# Sheet1.net
KiCad netlist of a schematic drawn in Altium Designer
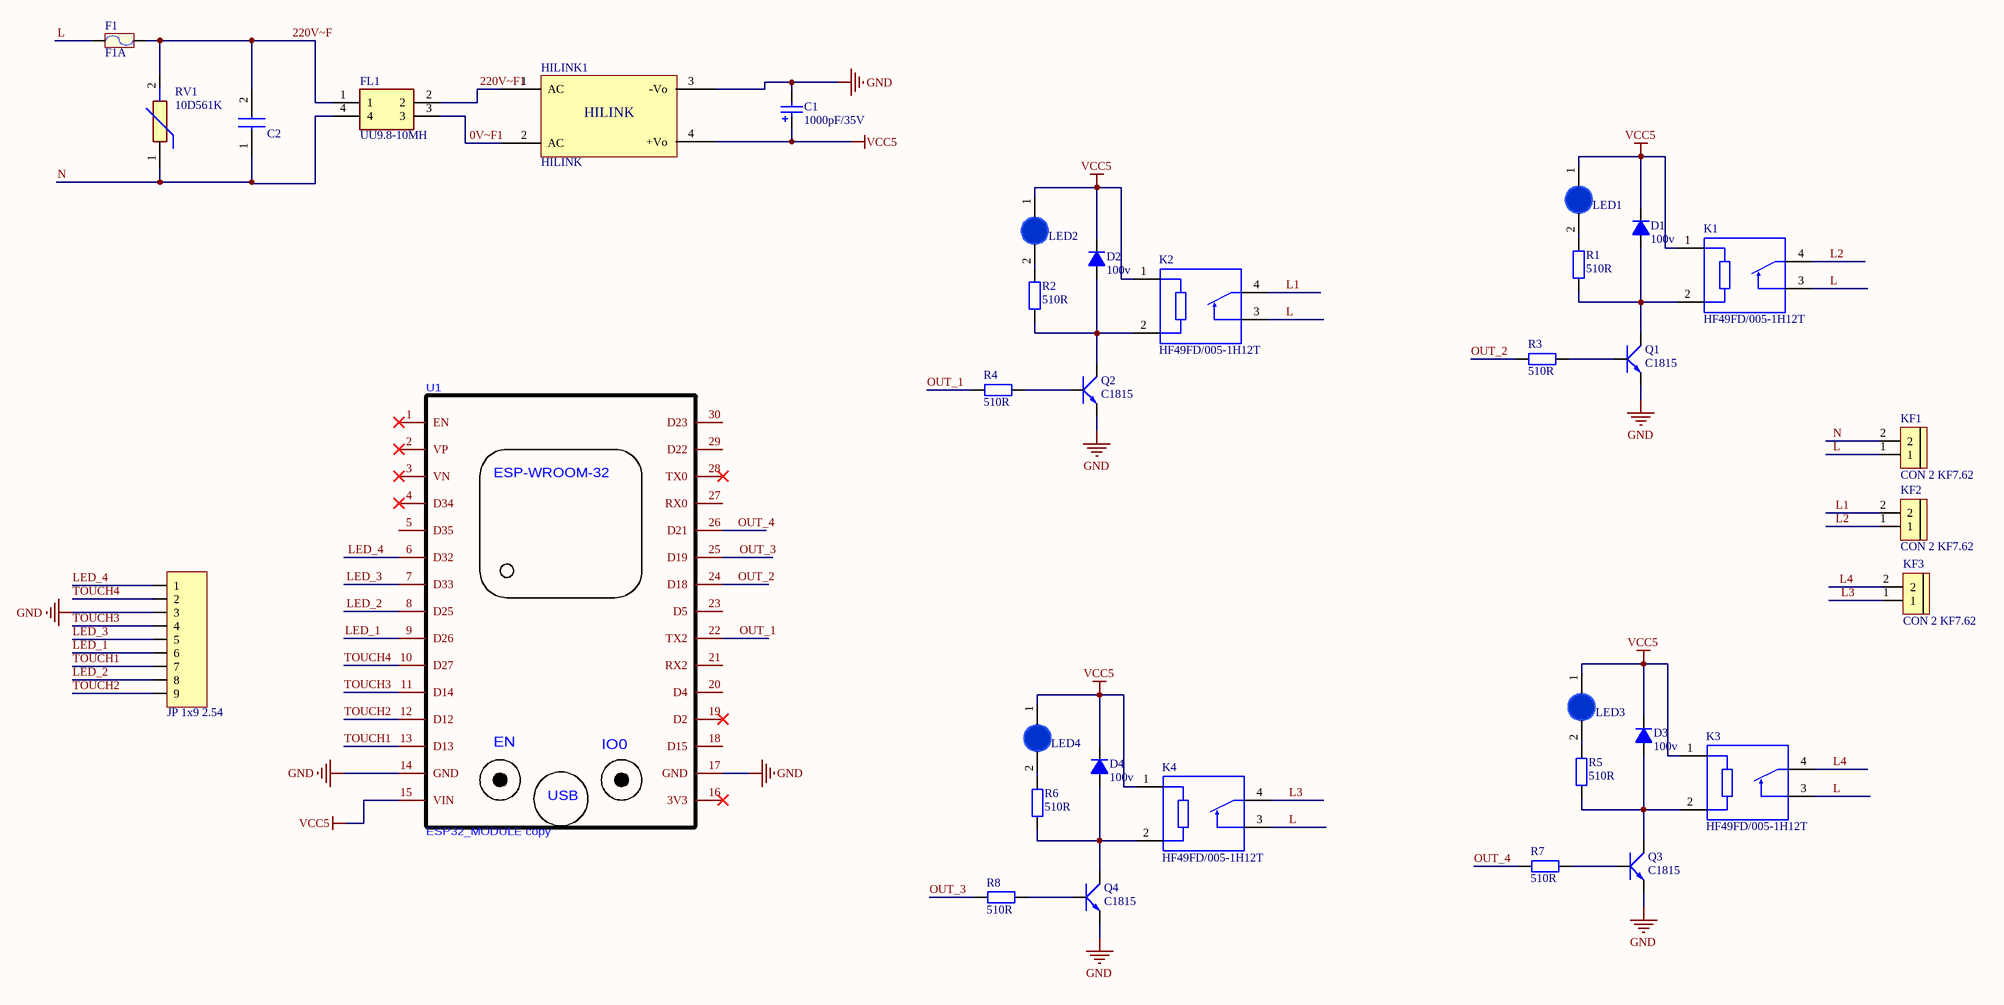
[diagram p0: Sheet1.SchDoc]

(export (version "E")
  (design (tool "Eeschema 10.0.6"))
  (components
    (comp (ref "C1")
      (value "1000pF/35V")
      (footprint "CP2/5")
      (description "Polarized Capacitor (Surface Mount)")
      (fields (field (name "Comment") "Cap Pol3") (field (name "PUBLISHER") "Altium Limited"))
      (libsource (lib "myLib_v1") (part "Cap Pol3"))
    )
    (comp (ref "C2")
      (value "R46KF3100JMP0K")
      (footprint "R46KF3100JMP0K")
      (description "Capacitor")
      (fields (field (name "MOUSER PART NUMBER") "80-R46KF3100JMP0K"))
      (libsource (lib "myLib_v1") (part "R46KF3100JMP0K"))
    )
    (comp (ref "D1")
      (value "100v")
      (footprint "DIODE 0.5A")
      (description "Cắm")
      (libsource (lib "Altium_Lib_by_KhueNguyenCreator") (part "Diode 1N4148"))
    )
    (comp (ref "D2")
      (value "100v")
      (footprint "DIODE 0.5A")
      (description "Cắm")
      (libsource (lib "Altium_Lib_by_KhueNguyenCreator") (part "Diode 1N4148"))
    )
    (comp (ref "D3")
      (value "100v")
      (footprint "DIODE 0.5A")
      (description "Cắm")
      (libsource (lib "Altium_Lib_by_KhueNguyenCreator") (part "Diode 1N4148"))
    )
    (comp (ref "D4")
      (value "100v")
      (footprint "DIODE 0.5A")
      (description "Cắm")
      (libsource (lib "Altium_Lib_by_KhueNguyenCreator") (part "Diode 1N4148"))
    )
    (comp (ref "F1")
      (value "F1A")
      (footprint "Fuse")
      (description "Fuse")
      (fields (field (name "DESIGNED BY") "VanDungEvn"))
      (libsource (lib "myLib_v1") (part "Fuse"))
    )
    (comp (ref "FL1")
      (value "UU9.8-10MH")
      (footprint "UU9810MH")
      (description "Filter")
      (libsource (lib "myLib_v1") (part "UU9.8-10MH"))
    )
    (comp (ref "HILINK1")
      (value "HILINK")
      (footprint "HILINK_1W")
      (libsource (lib "myLib_v1") (part "HILINK"))
    )
    (comp (ref "JP1")
      (value "JP 1x9 2.54")
      (footprint "JP 1x9 CT")
      (description "Cắm")
      (libsource (lib "Altium_Lib_by_KhueNguyenCreator") (part "JP 1x9 2.54 Cai Thang"))
    )
    (comp (ref "K1")
      (value "HF49FD/005-1H12T")
      (footprint "RELAY_HF49FD/005-1H12T")
      (description "Relay: electromagnetic; SPST-NO; Ucoil: 5VDC; 5A/250VAC; 5A/30VDC")
      (fields (field (name "MF") "Hongfa"))
      (libsource (lib "myLib_v1") (part "HF49FD/005-1H12T"))
    )
    (comp (ref "K2")
      (value "HF49FD/005-1H12T")
      (footprint "RELAY_HF49FD/005-1H12T")
      (description "Relay: electromagnetic; SPST-NO; Ucoil: 5VDC; 5A/250VAC; 5A/30VDC")
      (fields (field (name "MF") "Hongfa"))
      (libsource (lib "myLib_v1") (part "HF49FD/005-1H12T"))
    )
    (comp (ref "K3")
      (value "HF49FD/005-1H12T")
      (footprint "RELAY_HF49FD/005-1H12T")
      (description "Relay: electromagnetic; SPST-NO; Ucoil: 5VDC; 5A/250VAC; 5A/30VDC")
      (fields (field (name "MF") "Hongfa"))
      (libsource (lib "myLib_v1") (part "HF49FD/005-1H12T"))
    )
    (comp (ref "K4")
      (value "HF49FD/005-1H12T")
      (footprint "RELAY_HF49FD/005-1H12T")
      (description "Relay: electromagnetic; SPST-NO; Ucoil: 5VDC; 5A/250VAC; 5A/30VDC")
      (fields (field (name "MF") "Hongfa"))
      (libsource (lib "myLib_v1") (part "HF49FD/005-1H12T"))
    )
    (comp (ref "KF1")
      (value "CON 2 KF7.62")
      (footprint "CON 2 KF7.62")
      (description "Cắm")
      (libsource (lib "Altium_Lib_by_KhueNguyenCreator") (part "CON 2 KF7.62"))
    )
    (comp (ref "KF2")
      (value "CON 2 KF7.62")
      (footprint "CON 2 KF7.62")
      (description "Cắm")
      (libsource (lib "Altium_Lib_by_KhueNguyenCreator") (part "CON 2 KF7.62"))
    )
    (comp (ref "KF3")
      (value "CON 2 KF7.62")
      (footprint "CON 2 KF7.62")
      (description "Cắm")
      (libsource (lib "Altium_Lib_by_KhueNguyenCreator") (part "CON 2 KF7.62"))
    )
    (comp (ref "LED1")
      (value "LED 3mm")
      (footprint "LED-3MM-BLUE")
      (description "Cắm")
      (libsource (lib "myLib_v1") (part "LED 3mm Xanh Duong"))
    )
    (comp (ref "LED2")
      (value "LED 3mm")
      (footprint "LED-3MM-BLUE")
      (description "Cắm")
      (libsource (lib "myLib_v1") (part "LED 3mm Xanh Duong"))
    )
    (comp (ref "LED3")
      (value "LED 3mm")
      (footprint "LED-3MM-BLUE")
      (description "Cắm")
      (libsource (lib "myLib_v1") (part "LED 3mm Xanh Duong"))
    )
    (comp (ref "LED4")
      (value "LED 3mm")
      (footprint "LED-3MM-BLUE")
      (description "Cắm")
      (libsource (lib "myLib_v1") (part "LED 3mm Xanh Duong"))
    )
    (comp (ref "Q1")
      (value "C1815")
      (footprint "C1815_cam")
      (description "NPN 600mW, ECB")
      (libsource (lib "myLib_v1") (part "C1815"))
    )
    (comp (ref "Q2")
      (value "C1815")
      (footprint "C1815_cam")
      (description "NPN 600mW, ECB")
      (libsource (lib "myLib_v1") (part "C1815"))
    )
    (comp (ref "Q3")
      (value "C1815")
      (footprint "C1815_cam")
      (description "NPN 600mW, ECB")
      (libsource (lib "myLib_v1") (part "C1815"))
    )
    (comp (ref "Q4")
      (value "C1815")
      (footprint "C1815_cam")
      (description "NPN 600mW, ECB")
      (libsource (lib "myLib_v1") (part "C1815"))
    )
    (comp (ref "R1")
      (value "510R")
      (footprint "R1/4W")
      (description "Resistor 1/4W")
      (libsource (lib "myLib_v1") (part "R1/4W"))
    )
    (comp (ref "R2")
      (value "510R")
      (footprint "R1/4W")
      (description "Resistor 1/4W")
      (libsource (lib "myLib_v1") (part "R1/4W"))
    )
    (comp (ref "R3")
      (value "510R")
      (footprint "R1/4W")
      (description "Resistor 1/4W")
      (libsource (lib "myLib_v1") (part "R1/4W"))
    )
    (comp (ref "R4")
      (value "510R")
      (footprint "R1/4W")
      (description "Resistor 1/4W")
      (libsource (lib "myLib_v1") (part "R1/4W"))
    )
    (comp (ref "R5")
      (value "510R")
      (footprint "R1/4W")
      (description "Resistor 1/4W")
      (libsource (lib "myLib_v1") (part "R1/4W"))
    )
    (comp (ref "R6")
      (value "510R")
      (footprint "R1/4W")
      (description "Resistor 1/4W")
      (libsource (lib "myLib_v1") (part "R1/4W"))
    )
    (comp (ref "R7")
      (value "510R")
      (footprint "R1/4W")
      (description "Resistor 1/4W")
      (libsource (lib "myLib_v1") (part "R1/4W"))
    )
    (comp (ref "R8")
      (value "510R")
      (footprint "R1/4W")
      (description "Resistor 1/4W")
      (libsource (lib "myLib_v1") (part "R1/4W"))
    )
    (comp (ref "RV1")
      (value "10D561K")
      (footprint "10D561K")
      (description "Varistor")
      (fields
        (field (name "MANUFACTURER_PART_NUMBER") "MOV-10D561K")
        (field (name "MOUSER PART NUMBER") "652-MOV-10D561K")
      )
      (libsource (lib "myLib_v1") (part "10D561K"))
    )
    (comp (ref "U1")
      (value "ESP32_MODULE copy")
      (footprint "ESP32-WIFIMODULE-FOOTPRINT")
      (libsource (lib "myLib_v1") (part "ESP32_MODULE copy"))
    )
  )
  (nets
    (net (code "1") (name "/0V~F1") (class "Default")
      (node (ref "FL1") (pin "3") (pinfunction "3_3") (pintype "passive"))
      (node (ref "HILINK1") (pin "2") (pinfunction "AC_2") (pintype "passive"))
    )
    (net (code "2") (name "/220V~F") (class "Default")
      (node (ref "C2") (pin "2") (pinfunction "2_2") (pintype "passive"))
      (node (ref "F1") (pin "2") (pinfunction "2_2") (pintype "passive"))
      (node (ref "FL1") (pin "1") (pinfunction "1_1") (pintype "passive"))
      (node (ref "RV1") (pin "2") (pinfunction "2_2") (pintype "passive"))
    )
    (net (code "3") (name "/220V~F1") (class "Default")
      (node (ref "FL1") (pin "2") (pinfunction "2_2") (pintype "passive"))
      (node (ref "HILINK1") (pin "1") (pinfunction "AC_1") (pintype "passive"))
    )
    (net (code "4") (name "/L") (class "Default")
      (node (ref "F1") (pin "1") (pinfunction "1_1") (pintype "passive"))
      (node (ref "K1") (pin "3") (pinfunction "C2_3") (pintype "passive"))
      (node (ref "K2") (pin "3") (pinfunction "C2_3") (pintype "passive"))
      (node (ref "K3") (pin "3") (pinfunction "C2_3") (pintype "passive"))
      (node (ref "K4") (pin "3") (pinfunction "C2_3") (pintype "passive"))
      (node (ref "KF1") (pin "1") (pinfunction "1_1") (pintype "passive"))
    )
    (net (code "5") (name "/L1") (class "Default")
      (node (ref "K2") (pin "4") (pinfunction "C1_4") (pintype "passive"))
      (node (ref "KF2") (pin "2") (pinfunction "2_2") (pintype "passive"))
    )
    (net (code "6") (name "/L2") (class "Default")
      (node (ref "K1") (pin "4") (pinfunction "C1_4") (pintype "passive"))
      (node (ref "KF2") (pin "1") (pinfunction "1_1") (pintype "passive"))
    )
    (net (code "7") (name "/L3") (class "Default")
      (node (ref "K4") (pin "4") (pinfunction "C1_4") (pintype "passive"))
      (node (ref "KF3") (pin "1") (pinfunction "1_1") (pintype "passive"))
    )
    (net (code "8") (name "/L4") (class "Default")
      (node (ref "K3") (pin "4") (pinfunction "C1_4") (pintype "passive"))
      (node (ref "KF3") (pin "2") (pinfunction "2_2") (pintype "passive"))
    )
    (net (code "9") (name "/LED_1") (class "Default")
      (node (ref "JP1") (pin "6") (pinfunction "6_6") (pintype "passive"))
      (node (ref "U1") (pin "9") (pinfunction "D26_9") (pintype "passive"))
    )
    (net (code "10") (name "/LED_2") (class "Default")
      (node (ref "JP1") (pin "8") (pinfunction "8_8") (pintype "passive"))
      (node (ref "U1") (pin "8") (pinfunction "D25_8") (pintype "passive"))
    )
    (net (code "11") (name "/LED_3") (class "Default")
      (node (ref "JP1") (pin "5") (pinfunction "5_5") (pintype "passive"))
      (node (ref "U1") (pin "7") (pinfunction "D33_7") (pintype "passive"))
    )
    (net (code "12") (name "/LED_4") (class "Default")
      (node (ref "JP1") (pin "1") (pinfunction "1_1") (pintype "passive"))
      (node (ref "U1") (pin "6") (pinfunction "D32_6") (pintype "passive"))
    )
    (net (code "13") (name "/N") (class "Default")
      (node (ref "C2") (pin "1") (pinfunction "1_1") (pintype "passive"))
      (node (ref "FL1") (pin "4") (pinfunction "4_4") (pintype "passive"))
      (node (ref "KF1") (pin "2") (pinfunction "2_2") (pintype "passive"))
      (node (ref "RV1") (pin "1") (pinfunction "1_1") (pintype "passive"))
    )
    (net (code "14") (name "/OUT_1") (class "Default")
      (node (ref "R4") (pin "1") (pinfunction "1_1") (pintype "passive"))
      (node (ref "U1") (pin "22") (pinfunction "TX2_22") (pintype "passive"))
    )
    (net (code "15") (name "/OUT_2") (class "Default")
      (node (ref "R3") (pin "1") (pinfunction "1_1") (pintype "passive"))
      (node (ref "U1") (pin "24") (pinfunction "D18_24") (pintype "passive"))
    )
    (net (code "16") (name "/OUT_3") (class "Default")
      (node (ref "R8") (pin "1") (pinfunction "1_1") (pintype "passive"))
      (node (ref "U1") (pin "25") (pinfunction "D19_25") (pintype "passive"))
    )
    (net (code "17") (name "/OUT_4") (class "Default")
      (node (ref "R7") (pin "1") (pinfunction "1_1") (pintype "passive"))
      (node (ref "U1") (pin "26") (pinfunction "D21_26") (pintype "passive"))
    )
    (net (code "18") (name "/TOUCH1") (class "Default")
      (node (ref "JP1") (pin "7") (pinfunction "7_7") (pintype "passive"))
      (node (ref "U1") (pin "13") (pinfunction "D13_13") (pintype "passive"))
    )
    (net (code "19") (name "/TOUCH2") (class "Default")
      (node (ref "JP1") (pin "9") (pinfunction "9_9") (pintype "passive"))
      (node (ref "U1") (pin "12") (pinfunction "D12_12") (pintype "passive"))
    )
    (net (code "20") (name "/TOUCH3") (class "Default")
      (node (ref "JP1") (pin "4") (pinfunction "4_4") (pintype "passive"))
      (node (ref "U1") (pin "11") (pinfunction "D14_11") (pintype "passive"))
    )
    (net (code "21") (name "/TOUCH4") (class "Default")
      (node (ref "JP1") (pin "2") (pinfunction "2_2") (pintype "passive"))
      (node (ref "U1") (pin "10") (pinfunction "D27_10") (pintype "passive"))
    )
    (net (code "22") (name "GND") (class "Default")
      (node (ref "C1") (pin "2") (pinfunction "2_2") (pintype "passive"))
      (node (ref "HILINK1") (pin "3") (pinfunction "-Vo_3") (pintype "passive"))
      (node (ref "JP1") (pin "3") (pinfunction "3_3") (pintype "passive"))
      (node (ref "Q1") (pin "1") (pinfunction "E_1") (pintype "passive"))
      (node (ref "Q2") (pin "1") (pinfunction "E_1") (pintype "passive"))
      (node (ref "Q3") (pin "1") (pinfunction "E_1") (pintype "passive"))
      (node (ref "Q4") (pin "1") (pinfunction "E_1") (pintype "passive"))
      (node (ref "U1") (pin "14") (pinfunction "GND_14") (pintype "passive"))
      (node (ref "U1") (pin "17") (pinfunction "GND_17") (pintype "passive"))
    )
    (net (code "23") (name "Net-(D1-A)") (class "Default")
      (node (ref "D1") (pin "1") (pinfunction "A_1") (pintype "passive"))
      (node (ref "K1") (pin "2") (pinfunction "L2_2") (pintype "passive"))
      (node (ref "Q1") (pin "2") (pinfunction "C_2") (pintype "passive"))
      (node (ref "R1") (pin "2") (pinfunction "2_2") (pintype "passive"))
    )
    (net (code "24") (name "Net-(D2-A)") (class "Default")
      (node (ref "D2") (pin "1") (pinfunction "A_1") (pintype "passive"))
      (node (ref "K2") (pin "2") (pinfunction "L2_2") (pintype "passive"))
      (node (ref "Q2") (pin "2") (pinfunction "C_2") (pintype "passive"))
      (node (ref "R2") (pin "2") (pinfunction "2_2") (pintype "passive"))
    )
    (net (code "25") (name "Net-(D3-A)") (class "Default")
      (node (ref "D3") (pin "1") (pinfunction "A_1") (pintype "passive"))
      (node (ref "K3") (pin "2") (pinfunction "L2_2") (pintype "passive"))
      (node (ref "Q3") (pin "2") (pinfunction "C_2") (pintype "passive"))
      (node (ref "R5") (pin "2") (pinfunction "2_2") (pintype "passive"))
    )
    (net (code "26") (name "Net-(D4-A)") (class "Default")
      (node (ref "D4") (pin "1") (pinfunction "A_1") (pintype "passive"))
      (node (ref "K4") (pin "2") (pinfunction "L2_2") (pintype "passive"))
      (node (ref "Q4") (pin "2") (pinfunction "C_2") (pintype "passive"))
      (node (ref "R6") (pin "2") (pinfunction "2_2") (pintype "passive"))
    )
    (net (code "27") (name "Net-(LED1-K)") (class "Default")
      (node (ref "LED1") (pin "2") (pinfunction "K_2") (pintype "passive"))
      (node (ref "R1") (pin "1") (pinfunction "1_1") (pintype "passive"))
    )
    (net (code "28") (name "Net-(LED2-K)") (class "Default")
      (node (ref "LED2") (pin "2") (pinfunction "K_2") (pintype "passive"))
      (node (ref "R2") (pin "1") (pinfunction "1_1") (pintype "passive"))
    )
    (net (code "29") (name "Net-(LED3-K)") (class "Default")
      (node (ref "LED3") (pin "2") (pinfunction "K_2") (pintype "passive"))
      (node (ref "R5") (pin "1") (pinfunction "1_1") (pintype "passive"))
    )
    (net (code "30") (name "Net-(LED4-K)") (class "Default")
      (node (ref "LED4") (pin "2") (pinfunction "K_2") (pintype "passive"))
      (node (ref "R6") (pin "1") (pinfunction "1_1") (pintype "passive"))
    )
    (net (code "31") (name "Net-(Q1-B)") (class "Default")
      (node (ref "Q1") (pin "3") (pinfunction "B_3") (pintype "passive"))
      (node (ref "R3") (pin "2") (pinfunction "2_2") (pintype "passive"))
    )
    (net (code "32") (name "Net-(Q2-B)") (class "Default")
      (node (ref "Q2") (pin "3") (pinfunction "B_3") (pintype "passive"))
      (node (ref "R4") (pin "2") (pinfunction "2_2") (pintype "passive"))
    )
    (net (code "33") (name "Net-(Q3-B)") (class "Default")
      (node (ref "Q3") (pin "3") (pinfunction "B_3") (pintype "passive"))
      (node (ref "R7") (pin "2") (pinfunction "2_2") (pintype "passive"))
    )
    (net (code "34") (name "Net-(Q4-B)") (class "Default")
      (node (ref "Q4") (pin "3") (pinfunction "B_3") (pintype "passive"))
      (node (ref "R8") (pin "2") (pinfunction "2_2") (pintype "passive"))
    )
    (net (code "35") (name "VCC5") (class "Default")
      (node (ref "C1") (pin "1") (pinfunction "1_1") (pintype "passive"))
      (node (ref "D1") (pin "2") (pinfunction "K_2") (pintype "passive"))
      (node (ref "D2") (pin "2") (pinfunction "K_2") (pintype "passive"))
      (node (ref "D3") (pin "2") (pinfunction "K_2") (pintype "passive"))
      (node (ref "D4") (pin "2") (pinfunction "K_2") (pintype "passive"))
      (node (ref "HILINK1") (pin "4") (pinfunction "+Vo_4") (pintype "passive"))
      (node (ref "K1") (pin "1") (pinfunction "L1_1") (pintype "passive"))
      (node (ref "K2") (pin "1") (pinfunction "L1_1") (pintype "passive"))
      (node (ref "K3") (pin "1") (pinfunction "L1_1") (pintype "passive"))
      (node (ref "K4") (pin "1") (pinfunction "L1_1") (pintype "passive"))
      (node (ref "LED1") (pin "1") (pinfunction "A_1") (pintype "passive"))
      (node (ref "LED2") (pin "1") (pinfunction "A_1") (pintype "passive"))
      (node (ref "LED3") (pin "1") (pinfunction "A_1") (pintype "passive"))
      (node (ref "LED4") (pin "1") (pinfunction "A_1") (pintype "passive"))
      (node (ref "U1") (pin "15") (pinfunction "VIN_15") (pintype "passive"))
    )
    (net (code "36") (name "unconnected-(U1-3V3-Pad16)") (class "Default")
      (node (ref "U1") (pin "16") (pinfunction "3V3_16") (pintype "passive+no_connect"))
    )
    (net (code "37") (name "unconnected-(U1-D2-Pad19)") (class "Default")
      (node (ref "U1") (pin "19") (pinfunction "D2_19") (pintype "passive+no_connect"))
    )
    (net (code "38") (name "unconnected-(U1-D4-Pad20)") (class "Default")
      (node (ref "U1") (pin "20") (pinfunction "D4_20") (pintype "passive"))
    )
    (net (code "39") (name "unconnected-(U1-D5-Pad23)") (class "Default")
      (node (ref "U1") (pin "23") (pinfunction "D5_23") (pintype "passive"))
    )
    (net (code "40") (name "unconnected-(U1-D15-Pad18)") (class "Default")
      (node (ref "U1") (pin "18") (pinfunction "D15_18") (pintype "passive"))
    )
    (net (code "41") (name "unconnected-(U1-D22-Pad29)") (class "Default")
      (node (ref "U1") (pin "29") (pinfunction "D22_29") (pintype "passive"))
    )
    (net (code "42") (name "unconnected-(U1-D23-Pad30)") (class "Default")
      (node (ref "U1") (pin "30") (pinfunction "D23_30") (pintype "passive"))
    )
    (net (code "43") (name "unconnected-(U1-D34-Pad4)") (class "Default")
      (node (ref "U1") (pin "4") (pinfunction "D34_4") (pintype "passive+no_connect"))
    )
    (net (code "44") (name "unconnected-(U1-D35-Pad5)") (class "Default")
      (node (ref "U1") (pin "5") (pinfunction "D35_5") (pintype "passive"))
    )
    (net (code "45") (name "unconnected-(U1-EN-Pad1)") (class "Default")
      (node (ref "U1") (pin "1") (pinfunction "EN_1") (pintype "passive+no_connect"))
    )
    (net (code "46") (name "unconnected-(U1-RX0-Pad27)") (class "Default")
      (node (ref "U1") (pin "27") (pinfunction "RX0_27") (pintype "passive"))
    )
    (net (code "47") (name "unconnected-(U1-RX2-Pad21)") (class "Default")
      (node (ref "U1") (pin "21") (pinfunction "RX2_21") (pintype "passive"))
    )
    (net (code "48") (name "unconnected-(U1-TX0-Pad28)") (class "Default")
      (node (ref "U1") (pin "28") (pinfunction "TX0_28") (pintype "passive+no_connect"))
    )
    (net (code "49") (name "unconnected-(U1-VN-Pad3)") (class "Default")
      (node (ref "U1") (pin "3") (pinfunction "VN_3") (pintype "passive+no_connect"))
    )
    (net (code "50") (name "unconnected-(U1-VP-Pad2)") (class "Default")
      (node (ref "U1") (pin "2") (pinfunction "VP_2") (pintype "passive+no_connect"))
    )
  )
)
